# board.net
KiCad netlist of a schematic drawn in EAGLE
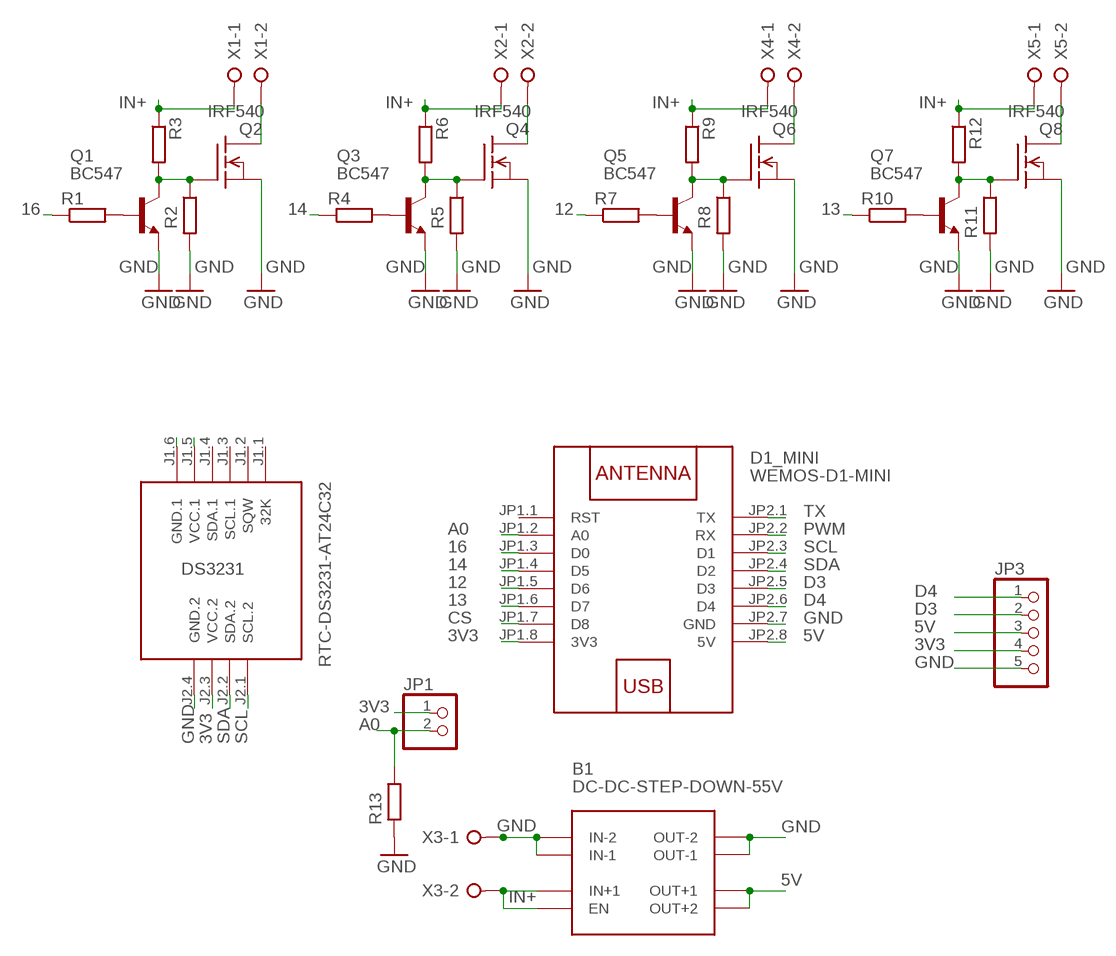
[diagram p0: schematic, sheet 1]

(export (version "E")
  (design (tool "Eeschema 10.0.6"))
  (components
    (comp (ref "B1")
      (value "DC-DC-STEP-DOWN-55V")
      (footprint "eagle-import:DC-DC-STEP-DOWN-55V")
      (libsource (lib "eagle-import") (part "DC-DC-STEP-DOWN-55V"))
    )
    (comp (ref "D1_MINI")
      (value "WEMOS-D1-MINI")
      (footprint "eagle-import:WEMOS-D1-MINI")
      (libsource (lib "eagle-import") (part "WEMOS-D1-MINI"))
    )
    (comp (ref "DS3231")
      (value "RTC-DS3231-AT24C32")
      (footprint "eagle-import:RTC-DS3231-AT24C32")
      (libsource (lib "eagle-import") (part "RTC-DS3231-AT24C32"))
    )
    (comp (ref "JP1")
      (value "PINHD-1X2")
      (footprint "eagle-import:1X02")
      (libsource (lib "eagle-import") (part "PINHD-1X2"))
    )
    (comp (ref "JP3")
      (value "PINHD-1X5")
      (footprint "eagle-import:1X05")
      (libsource (lib "eagle-import") (part "PINHD-1X5"))
    )
    (comp (ref "Q1")
      (value "BC547")
      (footprint "eagle-import:TO92")
      (libsource (lib "eagle-import") (part "BC547"))
    )
    (comp (ref "Q2")
      (value "IRF540")
      (footprint "eagle-import:TO220")
      (libsource (lib "eagle-import") (part "IRF540"))
    )
    (comp (ref "Q3")
      (value "BC547")
      (footprint "eagle-import:TO92")
      (libsource (lib "eagle-import") (part "BC547"))
    )
    (comp (ref "Q4")
      (value "IRF540")
      (footprint "eagle-import:TO220")
      (libsource (lib "eagle-import") (part "IRF540"))
    )
    (comp (ref "Q5")
      (value "BC547")
      (footprint "eagle-import:TO92")
      (libsource (lib "eagle-import") (part "BC547"))
    )
    (comp (ref "Q6")
      (value "IRF540")
      (footprint "eagle-import:TO220")
      (libsource (lib "eagle-import") (part "IRF540"))
    )
    (comp (ref "Q7")
      (value "BC547")
      (footprint "eagle-import:TO92")
      (libsource (lib "eagle-import") (part "BC547"))
    )
    (comp (ref "Q8")
      (value "IRF540")
      (footprint "eagle-import:TO220")
      (libsource (lib "eagle-import") (part "IRF540"))
    )
    (comp (ref "R1")
      (value "R-EU_0207/10")
      (footprint "eagle-import:0207_10")
      (libsource (lib "eagle-import") (part "R-EU_0207/10"))
    )
    (comp (ref "R2")
      (value "R-EU_0207/10")
      (footprint "eagle-import:0207_10")
      (libsource (lib "eagle-import") (part "R-EU_0207/10"))
    )
    (comp (ref "R3")
      (value "R-EU_0207/10")
      (footprint "eagle-import:0207_10")
      (libsource (lib "eagle-import") (part "R-EU_0207/10"))
    )
    (comp (ref "R4")
      (value "R-EU_0207/10")
      (footprint "eagle-import:0207_10")
      (libsource (lib "eagle-import") (part "R-EU_0207/10"))
    )
    (comp (ref "R5")
      (value "R-EU_0207/10")
      (footprint "eagle-import:0207_10")
      (libsource (lib "eagle-import") (part "R-EU_0207/10"))
    )
    (comp (ref "R6")
      (value "R-EU_0207/10")
      (footprint "eagle-import:0207_10")
      (libsource (lib "eagle-import") (part "R-EU_0207/10"))
    )
    (comp (ref "R7")
      (value "R-EU_0207/10")
      (footprint "eagle-import:0207_10")
      (libsource (lib "eagle-import") (part "R-EU_0207/10"))
    )
    (comp (ref "R8")
      (value "R-EU_0207/10")
      (footprint "eagle-import:0207_10")
      (libsource (lib "eagle-import") (part "R-EU_0207/10"))
    )
    (comp (ref "R9")
      (value "R-EU_0207/10")
      (footprint "eagle-import:0207_10")
      (libsource (lib "eagle-import") (part "R-EU_0207/10"))
    )
    (comp (ref "R10")
      (value "R-EU_0207/10")
      (footprint "eagle-import:0207_10")
      (libsource (lib "eagle-import") (part "R-EU_0207/10"))
    )
    (comp (ref "R11")
      (value "R-EU_0207/10")
      (footprint "eagle-import:0207_10")
      (libsource (lib "eagle-import") (part "R-EU_0207/10"))
    )
    (comp (ref "R12")
      (value "R-EU_0207/10")
      (footprint "eagle-import:0207_10")
      (libsource (lib "eagle-import") (part "R-EU_0207/10"))
    )
    (comp (ref "R13")
      (value "R-EU_0207/10")
      (footprint "eagle-import:0207_10")
      (libsource (lib "eagle-import") (part "R-EU_0207/10"))
    )
    (comp (ref "X1")
      (value "W237-02P")
      (footprint "eagle-import:W237-132")
      (libsource (lib "eagle-import") (part "W237-02P"))
    )
    (comp (ref "X2")
      (value "W237-02P")
      (footprint "eagle-import:W237-132")
      (libsource (lib "eagle-import") (part "W237-02P"))
    )
    (comp (ref "X3")
      (value "W237-02P")
      (footprint "eagle-import:W237-132")
      (libsource (lib "eagle-import") (part "W237-02P"))
    )
    (comp (ref "X4")
      (value "W237-02P")
      (footprint "eagle-import:W237-132")
      (libsource (lib "eagle-import") (part "W237-02P"))
    )
    (comp (ref "X5")
      (value "W237-02P")
      (footprint "eagle-import:W237-132")
      (libsource (lib "eagle-import") (part "W237-02P"))
    )
  )
  (nets
    (net (code "1") (name "/3V3") (class "Default")
      (node (ref "D1_MINI") (pin "JP1.8") (pinfunction "3V3_JP1.8") (pintype "power_in"))
      (node (ref "DS3231") (pin "J2.3") (pinfunction "VCC.2_J2.3") (pintype "power_in"))
      (node (ref "JP1") (pin "1") (pinfunction "1_1") (pintype "passive"))
      (node (ref "JP3") (pin "4") (pinfunction "4_4") (pintype "passive"))
    )
    (net (code "2") (name "/5V") (class "Default")
      (node (ref "B1") (pin "VOUT+1") (pinfunction "OUT+1_VOUT+1") (pintype "bidirectional"))
      (node (ref "B1") (pin "VOUT+2") (pinfunction "OUT+2_VOUT+2") (pintype "bidirectional"))
      (node (ref "D1_MINI") (pin "JP2.8") (pinfunction "5V_JP2.8") (pintype "power_in"))
      (node (ref "JP3") (pin "3") (pinfunction "3_3") (pintype "passive"))
    )
    (net (code "3") (name "/12") (class "Default")
      (node (ref "D1_MINI") (pin "JP1.5") (pinfunction "D6_JP1.5") (pintype "bidirectional"))
      (node (ref "R7") (pin "1") (pinfunction "1_1") (pintype "passive"))
    )
    (net (code "4") (name "/13") (class "Default")
      (node (ref "D1_MINI") (pin "JP1.6") (pinfunction "D7_JP1.6") (pintype "bidirectional"))
      (node (ref "R10") (pin "1") (pinfunction "1_1") (pintype "passive"))
    )
    (net (code "5") (name "/14") (class "Default")
      (node (ref "D1_MINI") (pin "JP1.4") (pinfunction "D5_JP1.4") (pintype "bidirectional"))
      (node (ref "R4") (pin "1") (pinfunction "1_1") (pintype "passive"))
    )
    (net (code "6") (name "/16") (class "Default")
      (node (ref "D1_MINI") (pin "JP1.3") (pinfunction "D0_JP1.3") (pintype "bidirectional"))
      (node (ref "R1") (pin "1") (pinfunction "1_1") (pintype "passive"))
    )
    (net (code "7") (name "/A0") (class "Default")
      (node (ref "D1_MINI") (pin "JP1.2") (pinfunction "A0_JP1.2") (pintype "bidirectional"))
      (node (ref "JP1") (pin "2") (pinfunction "2_2") (pintype "passive"))
      (node (ref "R13") (pin "1") (pinfunction "1_1") (pintype "passive"))
    )
    (net (code "8") (name "/CS") (class "Default")
      (node (ref "D1_MINI") (pin "JP1.7") (pinfunction "D8_JP1.7") (pintype "bidirectional"))
    )
    (net (code "9") (name "/D3") (class "Default")
      (node (ref "D1_MINI") (pin "JP2.5") (pinfunction "D3_JP2.5") (pintype "bidirectional"))
      (node (ref "JP3") (pin "2") (pinfunction "2_2") (pintype "passive"))
    )
    (net (code "10") (name "/D4") (class "Default")
      (node (ref "D1_MINI") (pin "JP2.6") (pinfunction "D4_JP2.6") (pintype "bidirectional"))
      (node (ref "JP3") (pin "1") (pinfunction "1_1") (pintype "passive"))
    )
    (net (code "11") (name "/IN+") (class "Default")
      (node (ref "B1") (pin "EN") (pinfunction "EN_EN") (pintype "bidirectional"))
      (node (ref "B1") (pin "VIN+") (pinfunction "IN+1_VIN+") (pintype "bidirectional"))
      (node (ref "R12") (pin "1") (pinfunction "1_1") (pintype "passive"))
      (node (ref "R3") (pin "1") (pinfunction "1_1") (pintype "passive"))
      (node (ref "R6") (pin "1") (pinfunction "1_1") (pintype "passive"))
      (node (ref "R9") (pin "1") (pinfunction "1_1") (pintype "passive"))
      (node (ref "X1") (pin "1") (pinfunction "KL_1") (pintype "passive"))
      (node (ref "X2") (pin "1") (pinfunction "KL_1") (pintype "passive"))
      (node (ref "X3") (pin "2") (pinfunction "KL_2") (pintype "passive"))
      (node (ref "X4") (pin "1") (pinfunction "KL_1") (pintype "passive"))
      (node (ref "X5") (pin "1") (pinfunction "KL_1") (pintype "passive"))
    )
    (net (code "12") (name "/PWM") (class "Default")
      (node (ref "D1_MINI") (pin "JP2.2") (pinfunction "RX_JP2.2") (pintype "bidirectional"))
    )
    (net (code "13") (name "/SCL") (class "Default")
      (node (ref "D1_MINI") (pin "JP2.3") (pinfunction "D1_JP2.3") (pintype "bidirectional"))
      (node (ref "DS3231") (pin "J2.1") (pinfunction "SCL.2_J2.1") (pintype "bidirectional"))
    )
    (net (code "14") (name "/SDA") (class "Default")
      (node (ref "D1_MINI") (pin "JP2.4") (pinfunction "D2_JP2.4") (pintype "bidirectional"))
      (node (ref "DS3231") (pin "J2.2") (pinfunction "SDA.2_J2.2") (pintype "bidirectional"))
    )
    (net (code "15") (name "/TX") (class "Default")
      (node (ref "D1_MINI") (pin "JP2.1") (pinfunction "TX_JP2.1") (pintype "bidirectional"))
    )
    (net (code "16") (name "GND") (class "Default")
      (node (ref "B1") (pin "VIN-1") (pinfunction "IN-1_VIN-1") (pintype "bidirectional"))
      (node (ref "B1") (pin "VIN-2") (pinfunction "IN-2_VIN-2") (pintype "bidirectional"))
      (node (ref "B1") (pin "VOUT-1") (pinfunction "OUT-1_VOUT-1") (pintype "bidirectional"))
      (node (ref "B1") (pin "VOUT-2") (pinfunction "OUT-2_VOUT-2") (pintype "bidirectional"))
      (node (ref "D1_MINI") (pin "JP2.7") (pinfunction "GND_JP2.7") (pintype "power_in"))
      (node (ref "DS3231") (pin "J2.4") (pinfunction "GND.2_J2.4") (pintype "power_in"))
      (node (ref "JP3") (pin "5") (pinfunction "5_5") (pintype "passive"))
      (node (ref "Q1") (pin "1") (pinfunction "E_1") (pintype "passive"))
      (node (ref "Q2") (pin "3") (pinfunction "S_3") (pintype "passive"))
      (node (ref "Q3") (pin "1") (pinfunction "E_1") (pintype "passive"))
      (node (ref "Q4") (pin "3") (pinfunction "S_3") (pintype "passive"))
      (node (ref "Q5") (pin "1") (pinfunction "E_1") (pintype "passive"))
      (node (ref "Q6") (pin "3") (pinfunction "S_3") (pintype "passive"))
      (node (ref "Q7") (pin "1") (pinfunction "E_1") (pintype "passive"))
      (node (ref "Q8") (pin "3") (pinfunction "S_3") (pintype "passive"))
      (node (ref "R11") (pin "2") (pinfunction "2_2") (pintype "passive"))
      (node (ref "R13") (pin "2") (pinfunction "2_2") (pintype "passive"))
      (node (ref "R2") (pin "2") (pinfunction "2_2") (pintype "passive"))
      (node (ref "R5") (pin "2") (pinfunction "2_2") (pintype "passive"))
      (node (ref "R8") (pin "2") (pinfunction "2_2") (pintype "passive"))
      (node (ref "X3") (pin "1") (pinfunction "KL_1") (pintype "passive"))
    )
    (net (code "17") (name "Net-(Q1-B)") (class "Default")
      (node (ref "Q1") (pin "2") (pinfunction "B_2") (pintype "passive"))
      (node (ref "R1") (pin "2") (pinfunction "2_2") (pintype "passive"))
    )
    (net (code "18") (name "Net-(Q1-C)") (class "Default")
      (node (ref "Q1") (pin "3") (pinfunction "C_3") (pintype "passive"))
      (node (ref "Q2") (pin "1") (pinfunction "G_1") (pintype "passive"))
      (node (ref "R2") (pin "1") (pinfunction "1_1") (pintype "passive"))
      (node (ref "R3") (pin "2") (pinfunction "2_2") (pintype "passive"))
    )
    (net (code "19") (name "Net-(Q2-D)") (class "Default")
      (node (ref "Q2") (pin "2") (pinfunction "D_2") (pintype "passive"))
      (node (ref "X1") (pin "2") (pinfunction "KL_2") (pintype "passive"))
    )
    (net (code "20") (name "Net-(Q3-B)") (class "Default")
      (node (ref "Q3") (pin "2") (pinfunction "B_2") (pintype "passive"))
      (node (ref "R4") (pin "2") (pinfunction "2_2") (pintype "passive"))
    )
    (net (code "21") (name "Net-(Q3-C)") (class "Default")
      (node (ref "Q3") (pin "3") (pinfunction "C_3") (pintype "passive"))
      (node (ref "Q4") (pin "1") (pinfunction "G_1") (pintype "passive"))
      (node (ref "R5") (pin "1") (pinfunction "1_1") (pintype "passive"))
      (node (ref "R6") (pin "2") (pinfunction "2_2") (pintype "passive"))
    )
    (net (code "22") (name "Net-(Q4-D)") (class "Default")
      (node (ref "Q4") (pin "2") (pinfunction "D_2") (pintype "passive"))
      (node (ref "X2") (pin "2") (pinfunction "KL_2") (pintype "passive"))
    )
    (net (code "23") (name "Net-(Q5-B)") (class "Default")
      (node (ref "Q5") (pin "2") (pinfunction "B_2") (pintype "passive"))
      (node (ref "R7") (pin "2") (pinfunction "2_2") (pintype "passive"))
    )
    (net (code "24") (name "Net-(Q5-C)") (class "Default")
      (node (ref "Q5") (pin "3") (pinfunction "C_3") (pintype "passive"))
      (node (ref "Q6") (pin "1") (pinfunction "G_1") (pintype "passive"))
      (node (ref "R8") (pin "1") (pinfunction "1_1") (pintype "passive"))
      (node (ref "R9") (pin "2") (pinfunction "2_2") (pintype "passive"))
    )
    (net (code "25") (name "Net-(Q6-D)") (class "Default")
      (node (ref "Q6") (pin "2") (pinfunction "D_2") (pintype "passive"))
      (node (ref "X4") (pin "2") (pinfunction "KL_2") (pintype "passive"))
    )
    (net (code "26") (name "Net-(Q7-B)") (class "Default")
      (node (ref "Q7") (pin "2") (pinfunction "B_2") (pintype "passive"))
      (node (ref "R10") (pin "2") (pinfunction "2_2") (pintype "passive"))
    )
    (net (code "27") (name "Net-(Q7-C)") (class "Default")
      (node (ref "Q7") (pin "3") (pinfunction "C_3") (pintype "passive"))
      (node (ref "Q8") (pin "1") (pinfunction "G_1") (pintype "passive"))
      (node (ref "R11") (pin "1") (pinfunction "1_1") (pintype "passive"))
      (node (ref "R12") (pin "2") (pinfunction "2_2") (pintype "passive"))
    )
    (net (code "28") (name "Net-(Q8-D)") (class "Default")
      (node (ref "Q8") (pin "2") (pinfunction "D_2") (pintype "passive"))
      (node (ref "X5") (pin "2") (pinfunction "KL_2") (pintype "passive"))
    )
    (net (code "29") (name "unconnected-(D1_MINI-RST-PadJP1.1)") (class "Default")
      (node (ref "D1_MINI") (pin "JP1.1") (pinfunction "RST_JP1.1") (pintype "bidirectional"))
    )
    (net (code "30") (name "unconnected-(DS3231-32K-PadJ1.1)") (class "Default")
      (node (ref "DS3231") (pin "J1.1") (pinfunction "32K_J1.1") (pintype "bidirectional"))
    )
    (net (code "31") (name "unconnected-(DS3231-GND.1-PadJ1.6)") (class "Default")
      (node (ref "DS3231") (pin "J1.6") (pinfunction "GND.1_J1.6") (pintype "power_in"))
    )
    (net (code "32") (name "unconnected-(DS3231-SCL.1-PadJ1.3)") (class "Default")
      (node (ref "DS3231") (pin "J1.3") (pinfunction "SCL.1_J1.3") (pintype "bidirectional"))
    )
    (net (code "33") (name "unconnected-(DS3231-SDA.1-PadJ1.4)") (class "Default")
      (node (ref "DS3231") (pin "J1.4") (pinfunction "SDA.1_J1.4") (pintype "bidirectional"))
    )
    (net (code "34") (name "unconnected-(DS3231-SQW-PadJ1.2)") (class "Default")
      (node (ref "DS3231") (pin "J1.2") (pinfunction "SQW_J1.2") (pintype "bidirectional"))
    )
    (net (code "35") (name "unconnected-(DS3231-VCC.1-PadJ1.5)") (class "Default")
      (node (ref "DS3231") (pin "J1.5") (pinfunction "VCC.1_J1.5") (pintype "power_in"))
    )
  )
)
